# Analog_Light_Project_Schematic_v1.net
KiCad netlist of a schematic drawn in EAGLE
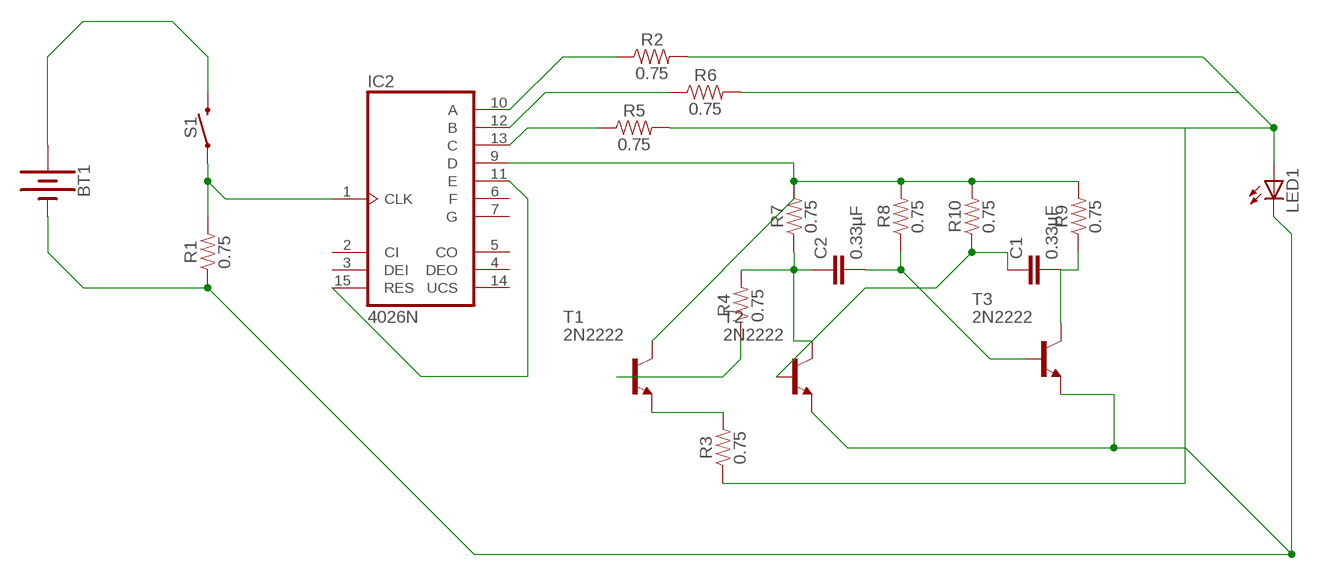
[diagram p0: schematic, sheet 1]

(export (version "E")
  (design (tool "Eeschema 10.0.6"))
  (components
    (comp (ref "BT1")
      (value "BATTERY-9V")
      (footprint "eagle-import:BATTCON_9V")
      (libsource (lib "eagle-import") (part "BATTERY-9V"))
    )
    (comp (ref "C1")
      (value "0.33µF")
      (footprint "eagle-import:0805")
      (libsource (lib "eagle-import") (part "0.33UF/330NF-0805-50V-10%"))
    )
    (comp (ref "C2")
      (value "0.33µF")
      (footprint "eagle-import:0805")
      (libsource (lib "eagle-import") (part "0.33UF/330NF-0805-50V-10%"))
    )
    (comp (ref "IC2")
      (value "4026N")
      (footprint "eagle-import:DIL16")
      (libsource (lib "eagle-import") (part "4026N"))
    )
    (comp (ref "LED1")
      (value "LED5MM")
      (footprint "eagle-import:LED5MM")
      (libsource (lib "eagle-import") (part "LED5MM"))
    )
    (comp (ref "R1")
      (value "0.75")
      (footprint "eagle-import:0805")
      (libsource (lib "eagle-import") (part "0.75OHM-0805-1/4W-1%"))
    )
    (comp (ref "R2")
      (value "0.75")
      (footprint "eagle-import:0805")
      (libsource (lib "eagle-import") (part "0.75OHM-0805-1/4W-1%"))
    )
    (comp (ref "R3")
      (value "0.75")
      (footprint "eagle-import:0805")
      (libsource (lib "eagle-import") (part "0.75OHM-0805-1/4W-1%"))
    )
    (comp (ref "R4")
      (value "0.75")
      (footprint "eagle-import:0805")
      (libsource (lib "eagle-import") (part "0.75OHM-0805-1/4W-1%"))
    )
    (comp (ref "R5")
      (value "0.75")
      (footprint "eagle-import:0805")
      (libsource (lib "eagle-import") (part "0.75OHM-0805-1/4W-1%"))
    )
    (comp (ref "R6")
      (value "0.75")
      (footprint "eagle-import:0805")
      (libsource (lib "eagle-import") (part "0.75OHM-0805-1/4W-1%"))
    )
    (comp (ref "R7")
      (value "0.75")
      (footprint "eagle-import:0805")
      (libsource (lib "eagle-import") (part "0.75OHM-0805-1/4W-1%"))
    )
    (comp (ref "R8")
      (value "0.75")
      (footprint "eagle-import:0805")
      (libsource (lib "eagle-import") (part "0.75OHM-0805-1/4W-1%"))
    )
    (comp (ref "R9")
      (value "0.75")
      (footprint "eagle-import:0805")
      (libsource (lib "eagle-import") (part "0.75OHM-0805-1/4W-1%"))
    )
    (comp (ref "R10")
      (value "0.75")
      (footprint "eagle-import:0805")
      (libsource (lib "eagle-import") (part "0.75OHM-0805-1/4W-1%"))
    )
    (comp (ref "S1")
      (value "MOMENTARY-SWITCH-SPST-PTH-6.0MM-KIT")
      (footprint "eagle-import:TACTILE_SWITCH_PTH_6.0MM_KIT")
      (libsource (lib "eagle-import") (part "MOMENTARY-SWITCH-SPST-PTH-6.0MM-KIT"))
    )
    (comp (ref "T1")
      (value "2N2222")
      (footprint "eagle-import:TO92-EBC-OVAL")
      (libsource (lib "eagle-import") (part "2N2222"))
    )
    (comp (ref "T2")
      (value "2N2222")
      (footprint "eagle-import:TO92-EBC-OVAL")
      (libsource (lib "eagle-import") (part "2N2222"))
    )
    (comp (ref "T3")
      (value "2N2222")
      (footprint "eagle-import:TO92-EBC-OVAL")
      (libsource (lib "eagle-import") (part "2N2222"))
    )
  )
  (nets
    (net (code "1") (name "Net-(C1-Pad1)") (class "Default")
      (node (ref "C1") (pin "1") (pinfunction "1_1") (pintype "passive"))
      (node (ref "R10") (pin "1") (pinfunction "1_1") (pintype "passive"))
      (node (ref "T2") (pin "B") (pinfunction "B_B") (pintype "passive"))
    )
    (net (code "2") (name "Net-(C1-Pad2)") (class "Default")
      (node (ref "C1") (pin "2") (pinfunction "2_2") (pintype "passive"))
      (node (ref "R9") (pin "1") (pinfunction "1_1") (pintype "passive"))
      (node (ref "T3") (pin "C") (pinfunction "C_C") (pintype "passive"))
    )
    (net (code "3") (name "Net-(C2-Pad1)") (class "Default")
      (node (ref "C2") (pin "1") (pinfunction "1_1") (pintype "passive"))
      (node (ref "R4") (pin "2") (pinfunction "2_2") (pintype "passive"))
      (node (ref "R7") (pin "1") (pinfunction "1_1") (pintype "passive"))
      (node (ref "T2") (pin "C") (pinfunction "C_C") (pintype "passive"))
    )
    (net (code "4") (name "Net-(C2-Pad2)") (class "Default")
      (node (ref "C2") (pin "2") (pinfunction "2_2") (pintype "passive"))
      (node (ref "R8") (pin "1") (pinfunction "1_1") (pintype "passive"))
      (node (ref "T3") (pin "B") (pinfunction "B_B") (pintype "passive"))
    )
    (net (code "5") (name "Net-(IC2A-A)") (class "Default")
      (node (ref "IC2") (pin "10") (pinfunction "A_10") (pintype "output"))
      (node (ref "R2") (pin "1") (pinfunction "1_1") (pintype "passive"))
    )
    (net (code "6") (name "Net-(IC2A-B)") (class "Default")
      (node (ref "IC2") (pin "12") (pinfunction "B_12") (pintype "output"))
      (node (ref "R6") (pin "1") (pinfunction "1_1") (pintype "passive"))
    )
    (net (code "7") (name "Net-(IC2A-C)") (class "Default")
      (node (ref "IC2") (pin "13") (pinfunction "C_13") (pintype "output"))
      (node (ref "R5") (pin "1") (pinfunction "1_1") (pintype "passive"))
    )
    (net (code "8") (name "Net-(IC2A-CLK)") (class "Default")
      (node (ref "IC2") (pin "1") (pinfunction "CLK_1") (pintype "input"))
      (node (ref "R1") (pin "2") (pinfunction "2_2") (pintype "passive"))
      (node (ref "S1") (pin "1") (pinfunction "1_1") (pintype "passive"))
    )
    (net (code "9") (name "Net-(IC2A-D)") (class "Default")
      (node (ref "IC2") (pin "9") (pinfunction "D_9") (pintype "output"))
      (node (ref "R10") (pin "2") (pinfunction "2_2") (pintype "passive"))
      (node (ref "R7") (pin "2") (pinfunction "2_2") (pintype "passive"))
      (node (ref "R8") (pin "2") (pinfunction "2_2") (pintype "passive"))
      (node (ref "R9") (pin "2") (pinfunction "2_2") (pintype "passive"))
      (node (ref "T1") (pin "C") (pinfunction "C_C") (pintype "passive"))
    )
    (net (code "10") (name "Net-(IC2A-E)") (class "Default")
      (node (ref "IC2") (pin "11") (pinfunction "E_11") (pintype "output"))
      (node (ref "IC2") (pin "15") (pinfunction "RES_15") (pintype "input"))
    )
    (net (code "11") (name "Net-(LED1-C)") (class "Default")
      (node (ref "BT1") (pin "-") (pinfunction "-_-") (pintype "power_in"))
      (node (ref "LED1") (pin "K") (pinfunction "C_K") (pintype "passive"))
      (node (ref "R1") (pin "1") (pinfunction "1_1") (pintype "passive"))
      (node (ref "T2") (pin "E") (pinfunction "E_E") (pintype "passive"))
      (node (ref "T3") (pin "E") (pinfunction "E_E") (pintype "passive"))
    )
    (net (code "12") (name "Net-(LED1-PadA)") (class "Default")
      (node (ref "LED1") (pin "A") (pinfunction "A_A") (pintype "passive"))
      (node (ref "R2") (pin "2") (pinfunction "2_2") (pintype "passive"))
      (node (ref "R3") (pin "1") (pinfunction "1_1") (pintype "passive"))
      (node (ref "R5") (pin "2") (pinfunction "2_2") (pintype "passive"))
      (node (ref "R6") (pin "2") (pinfunction "2_2") (pintype "passive"))
    )
    (net (code "13") (name "Net-(R3-Pad2)") (class "Default")
      (node (ref "R3") (pin "2") (pinfunction "2_2") (pintype "passive"))
      (node (ref "T1") (pin "E") (pinfunction "E_E") (pintype "passive"))
    )
    (net (code "14") (name "Net-(R4-Pad1)") (class "Default")
      (node (ref "R4") (pin "1") (pinfunction "1_1") (pintype "passive"))
      (node (ref "T1") (pin "B") (pinfunction "B_B") (pintype "passive"))
    )
    (net (code "15") (name "Net-(S1-2)") (class "Default")
      (node (ref "BT1") (pin "+") (pinfunction "+_+") (pintype "power_in"))
      (node (ref "S1") (pin "3") (pinfunction "2_3") (pintype "passive"))
    )
    (net (code "16") (name "unconnected-(IC2A-CI-Pad2)") (class "Default")
      (node (ref "IC2") (pin "2") (pinfunction "CI_2") (pintype "input"))
    )
    (net (code "17") (name "unconnected-(IC2A-CO-Pad5)") (class "Default")
      (node (ref "IC2") (pin "5") (pinfunction "CO_5") (pintype "output"))
    )
    (net (code "18") (name "unconnected-(IC2A-DEI-Pad3)") (class "Default")
      (node (ref "IC2") (pin "3") (pinfunction "DEI_3") (pintype "input"))
    )
    (net (code "19") (name "unconnected-(IC2A-DEO-Pad4)") (class "Default")
      (node (ref "IC2") (pin "4") (pinfunction "DEO_4") (pintype "output"))
    )
    (net (code "20") (name "unconnected-(IC2A-F-Pad6)") (class "Default")
      (node (ref "IC2") (pin "6") (pinfunction "F_6") (pintype "output"))
    )
    (net (code "21") (name "unconnected-(IC2A-G-Pad7)") (class "Default")
      (node (ref "IC2") (pin "7") (pinfunction "G_7") (pintype "output"))
    )
    (net (code "22") (name "unconnected-(IC2A-UCS-Pad14)") (class "Default")
      (node (ref "IC2") (pin "14") (pinfunction "UCS_14") (pintype "output"))
    )
  )
)
